# Wio_MB128_Test_rev_B.net
KiCad netlist of a schematic drawn in EAGLE
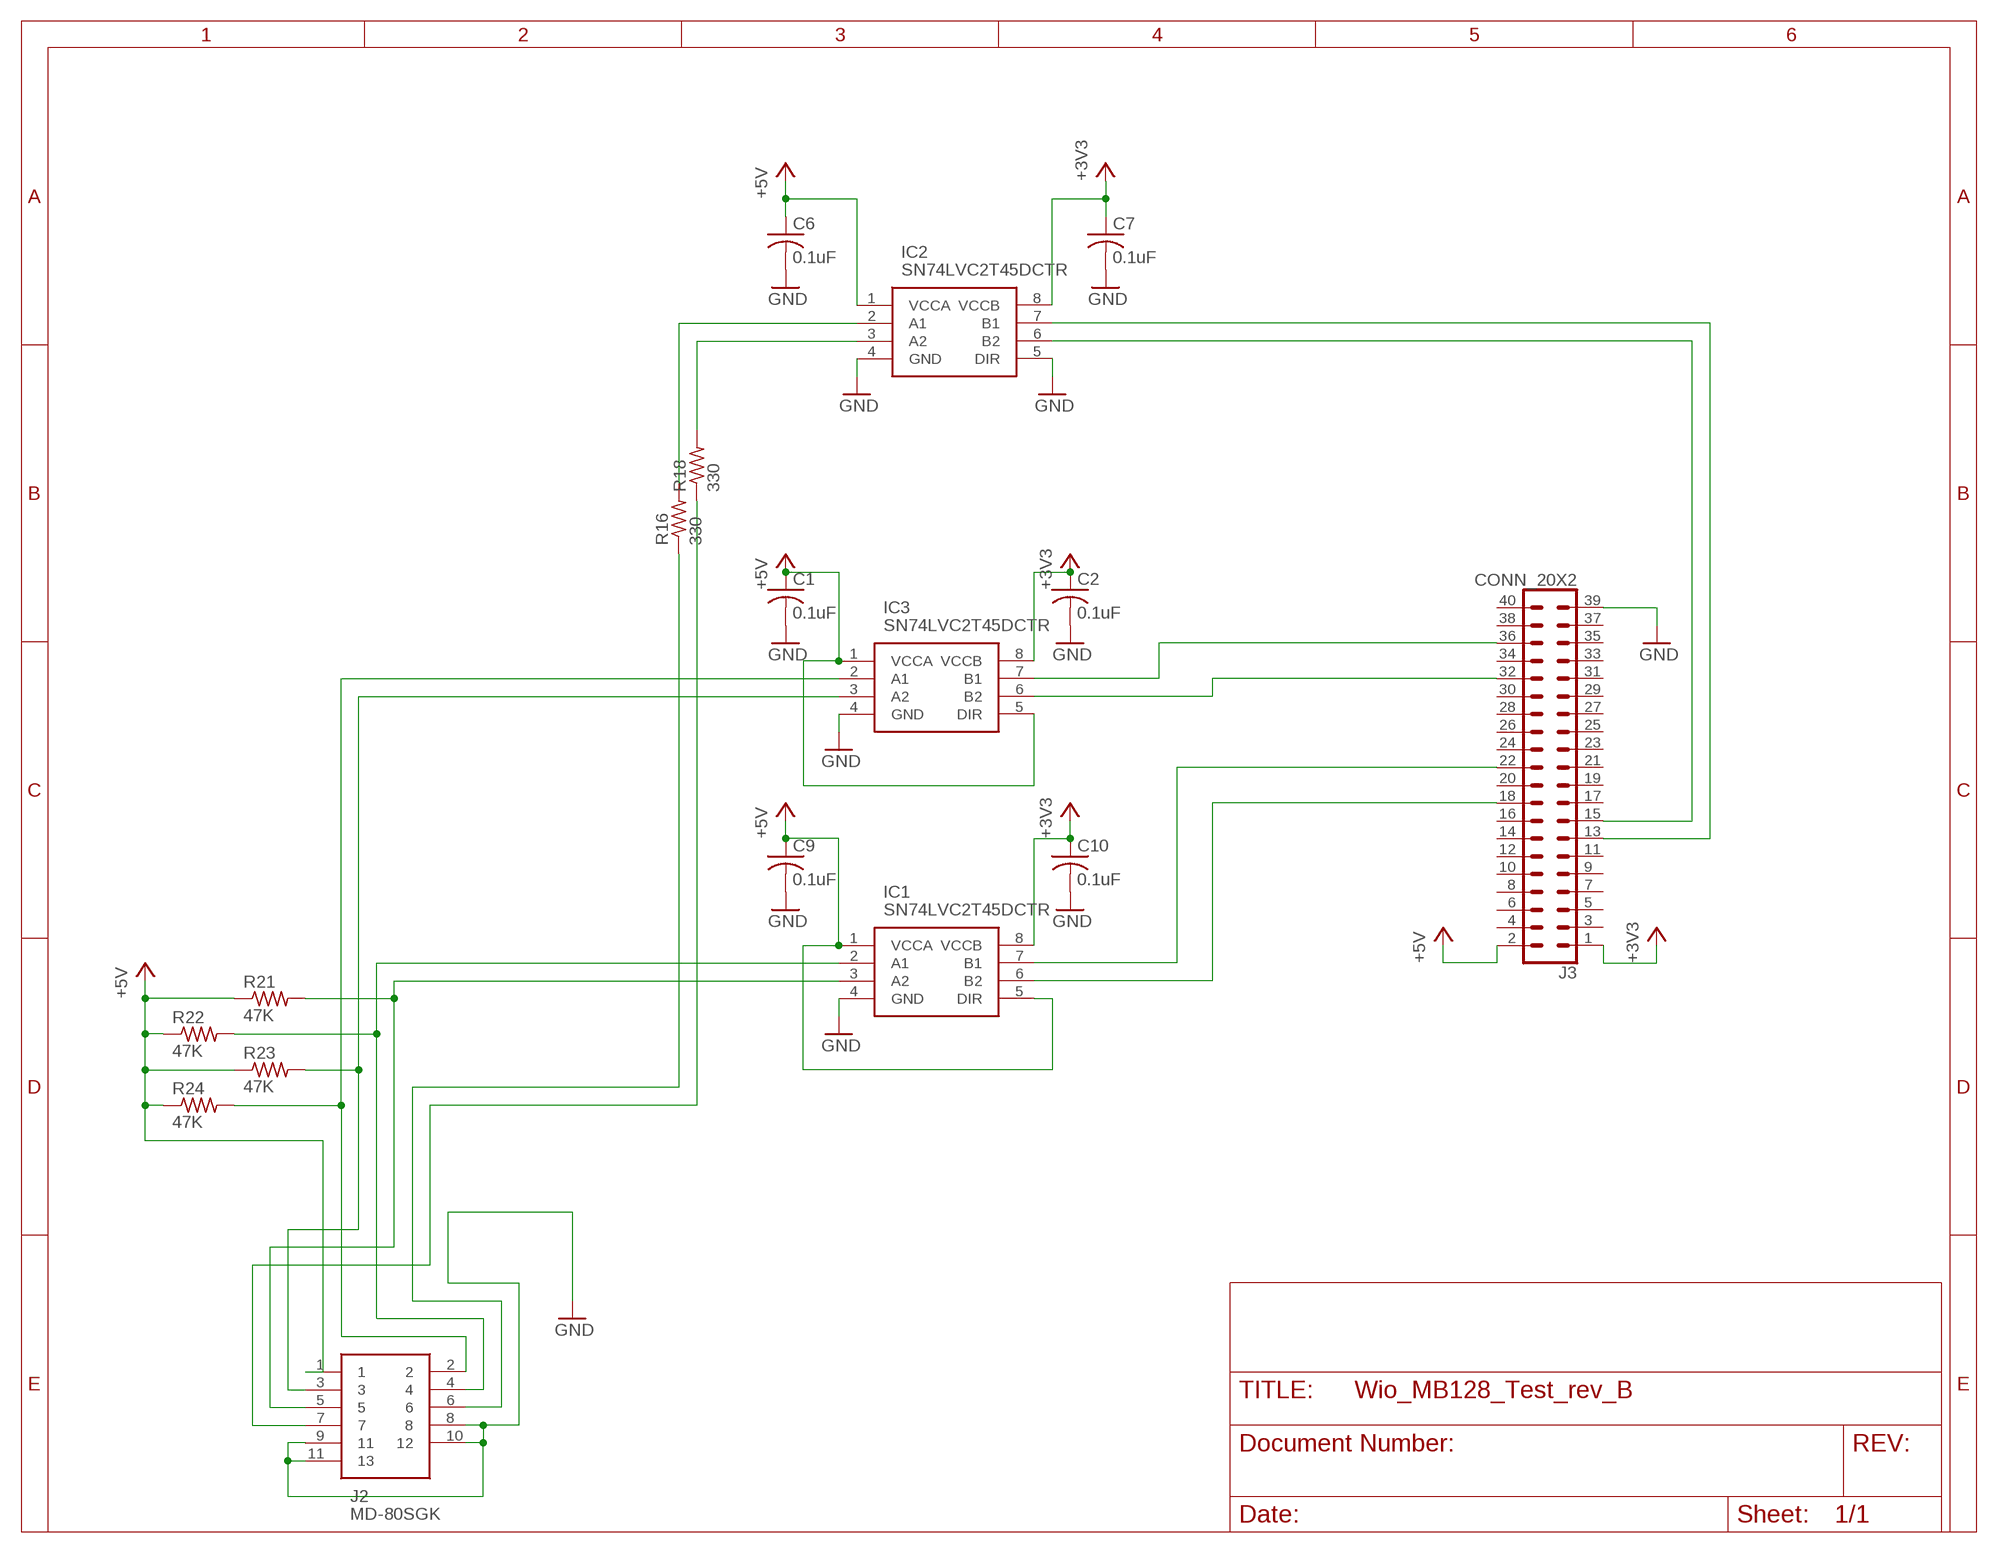
[diagram p0: schematic, sheet 1]

(export (version "E")
  (design (tool "Eeschema 10.0.6"))
  (components
    (comp (ref "C1")
      (value "0.1uF")
      (footprint "eagle-import:C0603")
      (libsource (lib "eagle-import") (part "C-USC0603"))
    )
    (comp (ref "C2")
      (value "0.1uF")
      (footprint "eagle-import:C0603")
      (libsource (lib "eagle-import") (part "C-USC0603"))
    )
    (comp (ref "C6")
      (value "0.1uF")
      (footprint "eagle-import:C0603")
      (libsource (lib "eagle-import") (part "C-USC0603"))
    )
    (comp (ref "C7")
      (value "0.1uF")
      (footprint "eagle-import:C0603")
      (libsource (lib "eagle-import") (part "C-USC0603"))
    )
    (comp (ref "C9")
      (value "0.1uF")
      (footprint "eagle-import:C0603")
      (libsource (lib "eagle-import") (part "C-USC0603"))
    )
    (comp (ref "C10")
      (value "0.1uF")
      (footprint "eagle-import:C0603")
      (libsource (lib "eagle-import") (part "C-USC0603"))
    )
    (comp (ref "IC1")
      (value "SN74LVC2T45DCTR")
      (footprint "eagle-import:SOP65P400X130-8N")
      (fields
        (field (name "MOUSER_PART_NUMBER") "595-SN74LVC2T45DCTR")
        (field (name "RS_PART_NUMBER") "9213022")
      )
      (libsource (lib "eagle-import") (part "SN74LVC2T45DCTR"))
    )
    (comp (ref "IC2")
      (value "SN74LVC2T45DCTR")
      (footprint "eagle-import:SOP65P400X130-8N")
      (fields
        (field (name "MOUSER_PART_NUMBER") "595-SN74LVC2T45DCTR")
        (field (name "RS_PART_NUMBER") "9213022")
      )
      (libsource (lib "eagle-import") (part "SN74LVC2T45DCTR"))
    )
    (comp (ref "IC3")
      (value "SN74LVC2T45DCTR")
      (footprint "eagle-import:SOP65P400X130-8N")
      (fields
        (field (name "MOUSER_PART_NUMBER") "595-SN74LVC2T45DCTR")
        (field (name "RS_PART_NUMBER") "9213022")
      )
      (libsource (lib "eagle-import") (part "SN74LVC2T45DCTR"))
    )
    (comp (ref "J2")
      (value "MD-80SGK")
      (footprint "eagle-import:MD80SGK")
      (fields (field (name "MOUSER_PART_NUMBER") "490-MD-80SGK"))
      (libsource (lib "eagle-import") (part "MD-80SGK"))
    )
    (comp (ref "J3")
      (value "CONN_20X2")
      (footprint "eagle-import:2X20")
      (libsource (lib "eagle-import") (part "CONN_20X2"))
    )
    (comp (ref "R16")
      (value "330")
      (footprint "eagle-import:R0603")
      (libsource (lib "eagle-import") (part "R-US_R0603"))
    )
    (comp (ref "R18")
      (value "330")
      (footprint "eagle-import:R0603")
      (libsource (lib "eagle-import") (part "R-US_R0603"))
    )
    (comp (ref "R21")
      (value "47K")
      (footprint "eagle-import:R0603")
      (libsource (lib "eagle-import") (part "R-US_R0603"))
    )
    (comp (ref "R22")
      (value "47K")
      (footprint "eagle-import:R0603")
      (libsource (lib "eagle-import") (part "R-US_R0603"))
    )
    (comp (ref "R23")
      (value "47K")
      (footprint "eagle-import:R0603")
      (libsource (lib "eagle-import") (part "R-US_R0603"))
    )
    (comp (ref "R24")
      (value "47K")
      (footprint "eagle-import:R0603")
      (libsource (lib "eagle-import") (part "R-US_R0603"))
    )
  )
  (nets
    (net (code "1") (name "+3V3") (class "Default")
      (node (ref "C10") (pin "1") (pinfunction "1_1") (pintype "passive"))
      (node (ref "C2") (pin "1") (pinfunction "1_1") (pintype "passive"))
      (node (ref "C7") (pin "1") (pinfunction "1_1") (pintype "passive"))
      (node (ref "IC1") (pin "8") (pinfunction "VCCB_8") (pintype "power_in"))
      (node (ref "IC2") (pin "8") (pinfunction "VCCB_8") (pintype "power_in"))
      (node (ref "IC3") (pin "8") (pinfunction "VCCB_8") (pintype "power_in"))
      (node (ref "J3") (pin "1") (pinfunction "1_1") (pintype "passive"))
    )
    (net (code "2") (name "+5V") (class "Default")
      (node (ref "C1") (pin "1") (pinfunction "1_1") (pintype "passive"))
      (node (ref "C6") (pin "1") (pinfunction "1_1") (pintype "passive"))
      (node (ref "C9") (pin "1") (pinfunction "1_1") (pintype "passive"))
      (node (ref "IC1") (pin "1") (pinfunction "VCCA_1") (pintype "power_in"))
      (node (ref "IC1") (pin "5") (pinfunction "DIR_5") (pintype "bidirectional"))
      (node (ref "IC2") (pin "1") (pinfunction "VCCA_1") (pintype "power_in"))
      (node (ref "IC3") (pin "1") (pinfunction "VCCA_1") (pintype "power_in"))
      (node (ref "IC3") (pin "5") (pinfunction "DIR_5") (pintype "bidirectional"))
      (node (ref "J2") (pin "1") (pinfunction "1_1") (pintype "bidirectional"))
      (node (ref "J3") (pin "2") (pinfunction "2_2") (pintype "passive"))
      (node (ref "R21") (pin "1") (pinfunction "1_1") (pintype "passive"))
      (node (ref "R22") (pin "1") (pinfunction "1_1") (pintype "passive"))
      (node (ref "R23") (pin "1") (pinfunction "1_1") (pintype "passive"))
      (node (ref "R24") (pin "1") (pinfunction "1_1") (pintype "passive"))
    )
    (net (code "3") (name "GND") (class "Default")
      (node (ref "C1") (pin "2") (pinfunction "2_2") (pintype "passive"))
      (node (ref "C10") (pin "2") (pinfunction "2_2") (pintype "passive"))
      (node (ref "C2") (pin "2") (pinfunction "2_2") (pintype "passive"))
      (node (ref "C6") (pin "2") (pinfunction "2_2") (pintype "passive"))
      (node (ref "C7") (pin "2") (pinfunction "2_2") (pintype "passive"))
      (node (ref "C9") (pin "2") (pinfunction "2_2") (pintype "passive"))
      (node (ref "IC1") (pin "4") (pinfunction "GND_4") (pintype "power_in"))
      (node (ref "IC2") (pin "4") (pinfunction "GND_4") (pintype "power_in"))
      (node (ref "IC2") (pin "5") (pinfunction "DIR_5") (pintype "bidirectional"))
      (node (ref "IC3") (pin "4") (pinfunction "GND_4") (pintype "power_in"))
      (node (ref "J2") (pin "10") (pinfunction "12_10") (pintype "bidirectional"))
      (node (ref "J2") (pin "11") (pinfunction "13_11") (pintype "bidirectional"))
      (node (ref "J2") (pin "8") (pinfunction "8_8") (pintype "bidirectional"))
      (node (ref "J2") (pin "9") (pinfunction "11_9") (pintype "bidirectional"))
      (node (ref "J3") (pin "39") (pinfunction "39_39") (pintype "passive"))
    )
    (net (code "4") (name "Net-(IC1-A1)") (class "Default")
      (node (ref "IC1") (pin "2") (pinfunction "A1_2") (pintype "bidirectional"))
      (node (ref "J2") (pin "4") (pinfunction "4_4") (pintype "bidirectional"))
      (node (ref "R22") (pin "2") (pinfunction "2_2") (pintype "passive"))
    )
    (net (code "5") (name "Net-(IC1-A2)") (class "Default")
      (node (ref "IC1") (pin "3") (pinfunction "A2_3") (pintype "bidirectional"))
      (node (ref "J2") (pin "5") (pinfunction "5_5") (pintype "bidirectional"))
      (node (ref "R21") (pin "2") (pinfunction "2_2") (pintype "passive"))
    )
    (net (code "6") (name "Net-(IC1-B1)") (class "Default")
      (node (ref "IC1") (pin "7") (pinfunction "B1_7") (pintype "bidirectional"))
      (node (ref "J3") (pin "22") (pinfunction "22_22") (pintype "passive"))
    )
    (net (code "7") (name "Net-(IC1-B2)") (class "Default")
      (node (ref "IC1") (pin "6") (pinfunction "B2_6") (pintype "bidirectional"))
      (node (ref "J3") (pin "18") (pinfunction "18_18") (pintype "passive"))
    )
    (net (code "8") (name "Net-(IC2-A1)") (class "Default")
      (node (ref "IC2") (pin "2") (pinfunction "A1_2") (pintype "bidirectional"))
      (node (ref "R16") (pin "2") (pinfunction "2_2") (pintype "passive"))
    )
    (net (code "9") (name "Net-(IC2-A2)") (class "Default")
      (node (ref "IC2") (pin "3") (pinfunction "A2_3") (pintype "bidirectional"))
      (node (ref "R18") (pin "2") (pinfunction "2_2") (pintype "passive"))
    )
    (net (code "10") (name "Net-(IC2-B1)") (class "Default")
      (node (ref "IC2") (pin "7") (pinfunction "B1_7") (pintype "bidirectional"))
      (node (ref "J3") (pin "13") (pinfunction "13_13") (pintype "passive"))
    )
    (net (code "11") (name "Net-(IC2-B2)") (class "Default")
      (node (ref "IC2") (pin "6") (pinfunction "B2_6") (pintype "bidirectional"))
      (node (ref "J3") (pin "15") (pinfunction "15_15") (pintype "passive"))
    )
    (net (code "12") (name "Net-(IC3-A1)") (class "Default")
      (node (ref "IC3") (pin "2") (pinfunction "A1_2") (pintype "bidirectional"))
      (node (ref "J2") (pin "2") (pinfunction "2_2") (pintype "bidirectional"))
      (node (ref "R24") (pin "2") (pinfunction "2_2") (pintype "passive"))
    )
    (net (code "13") (name "Net-(IC3-A2)") (class "Default")
      (node (ref "IC3") (pin "3") (pinfunction "A2_3") (pintype "bidirectional"))
      (node (ref "J2") (pin "3") (pinfunction "3_3") (pintype "bidirectional"))
      (node (ref "R23") (pin "2") (pinfunction "2_2") (pintype "passive"))
    )
    (net (code "14") (name "Net-(IC3-B1)") (class "Default")
      (node (ref "IC3") (pin "7") (pinfunction "B1_7") (pintype "bidirectional"))
      (node (ref "J3") (pin "36") (pinfunction "36_36") (pintype "passive"))
    )
    (net (code "15") (name "Net-(IC3-B2)") (class "Default")
      (node (ref "IC3") (pin "6") (pinfunction "B2_6") (pintype "bidirectional"))
      (node (ref "J3") (pin "32") (pinfunction "32_32") (pintype "passive"))
    )
    (net (code "16") (name "Net-(J2-Pad6)") (class "Default")
      (node (ref "J2") (pin "6") (pinfunction "6_6") (pintype "bidirectional"))
      (node (ref "R16") (pin "1") (pinfunction "1_1") (pintype "passive"))
    )
    (net (code "17") (name "Net-(J2-Pad7)") (class "Default")
      (node (ref "J2") (pin "7") (pinfunction "7_7") (pintype "bidirectional"))
      (node (ref "R18") (pin "1") (pinfunction "1_1") (pintype "passive"))
    )
    (net (code "18") (name "unconnected-(J3-Pad3)") (class "Default")
      (node (ref "J3") (pin "3") (pinfunction "3_3") (pintype "passive"))
    )
    (net (code "19") (name "unconnected-(J3-Pad4)") (class "Default")
      (node (ref "J3") (pin "4") (pinfunction "4_4") (pintype "passive"))
    )
    (net (code "20") (name "unconnected-(J3-Pad5)") (class "Default")
      (node (ref "J3") (pin "5") (pinfunction "5_5") (pintype "passive"))
    )
    (net (code "21") (name "unconnected-(J3-Pad6)") (class "Default")
      (node (ref "J3") (pin "6") (pinfunction "6_6") (pintype "passive"))
    )
    (net (code "22") (name "unconnected-(J3-Pad7)") (class "Default")
      (node (ref "J3") (pin "7") (pinfunction "7_7") (pintype "passive"))
    )
    (net (code "23") (name "unconnected-(J3-Pad8)") (class "Default")
      (node (ref "J3") (pin "8") (pinfunction "8_8") (pintype "passive"))
    )
    (net (code "24") (name "unconnected-(J3-Pad9)") (class "Default")
      (node (ref "J3") (pin "9") (pinfunction "9_9") (pintype "passive"))
    )
    (net (code "25") (name "unconnected-(J3-Pad10)") (class "Default")
      (node (ref "J3") (pin "10") (pinfunction "10_10") (pintype "passive"))
    )
    (net (code "26") (name "unconnected-(J3-Pad11)") (class "Default")
      (node (ref "J3") (pin "11") (pinfunction "11_11") (pintype "passive"))
    )
    (net (code "27") (name "unconnected-(J3-Pad12)") (class "Default")
      (node (ref "J3") (pin "12") (pinfunction "12_12") (pintype "passive"))
    )
    (net (code "28") (name "unconnected-(J3-Pad14)") (class "Default")
      (node (ref "J3") (pin "14") (pinfunction "14_14") (pintype "passive"))
    )
    (net (code "29") (name "unconnected-(J3-Pad16)") (class "Default")
      (node (ref "J3") (pin "16") (pinfunction "16_16") (pintype "passive"))
    )
    (net (code "30") (name "unconnected-(J3-Pad17)") (class "Default")
      (node (ref "J3") (pin "17") (pinfunction "17_17") (pintype "passive"))
    )
    (net (code "31") (name "unconnected-(J3-Pad19)") (class "Default")
      (node (ref "J3") (pin "19") (pinfunction "19_19") (pintype "passive"))
    )
    (net (code "32") (name "unconnected-(J3-Pad20)") (class "Default")
      (node (ref "J3") (pin "20") (pinfunction "20_20") (pintype "passive"))
    )
    (net (code "33") (name "unconnected-(J3-Pad21)") (class "Default")
      (node (ref "J3") (pin "21") (pinfunction "21_21") (pintype "passive"))
    )
    (net (code "34") (name "unconnected-(J3-Pad23)") (class "Default")
      (node (ref "J3") (pin "23") (pinfunction "23_23") (pintype "passive"))
    )
    (net (code "35") (name "unconnected-(J3-Pad24)") (class "Default")
      (node (ref "J3") (pin "24") (pinfunction "24_24") (pintype "passive"))
    )
    (net (code "36") (name "unconnected-(J3-Pad25)") (class "Default")
      (node (ref "J3") (pin "25") (pinfunction "25_25") (pintype "passive"))
    )
    (net (code "37") (name "unconnected-(J3-Pad26)") (class "Default")
      (node (ref "J3") (pin "26") (pinfunction "26_26") (pintype "passive"))
    )
    (net (code "38") (name "unconnected-(J3-Pad27)") (class "Default")
      (node (ref "J3") (pin "27") (pinfunction "27_27") (pintype "passive"))
    )
    (net (code "39") (name "unconnected-(J3-Pad28)") (class "Default")
      (node (ref "J3") (pin "28") (pinfunction "28_28") (pintype "passive"))
    )
    (net (code "40") (name "unconnected-(J3-Pad29)") (class "Default")
      (node (ref "J3") (pin "29") (pinfunction "29_29") (pintype "passive"))
    )
    (net (code "41") (name "unconnected-(J3-Pad30)") (class "Default")
      (node (ref "J3") (pin "30") (pinfunction "30_30") (pintype "passive"))
    )
    (net (code "42") (name "unconnected-(J3-Pad31)") (class "Default")
      (node (ref "J3") (pin "31") (pinfunction "31_31") (pintype "passive"))
    )
    (net (code "43") (name "unconnected-(J3-Pad33)") (class "Default")
      (node (ref "J3") (pin "33") (pinfunction "33_33") (pintype "passive"))
    )
    (net (code "44") (name "unconnected-(J3-Pad34)") (class "Default")
      (node (ref "J3") (pin "34") (pinfunction "34_34") (pintype "passive"))
    )
    (net (code "45") (name "unconnected-(J3-Pad35)") (class "Default")
      (node (ref "J3") (pin "35") (pinfunction "35_35") (pintype "passive"))
    )
    (net (code "46") (name "unconnected-(J3-Pad37)") (class "Default")
      (node (ref "J3") (pin "37") (pinfunction "37_37") (pintype "passive"))
    )
    (net (code "47") (name "unconnected-(J3-Pad38)") (class "Default")
      (node (ref "J3") (pin "38") (pinfunction "38_38") (pintype "passive"))
    )
    (net (code "48") (name "unconnected-(J3-Pad40)") (class "Default")
      (node (ref "J3") (pin "40") (pinfunction "40_40") (pintype "passive"))
    )
  )
)
